# light_controller.net
KiCad netlist of a schematic drawn in EAGLE
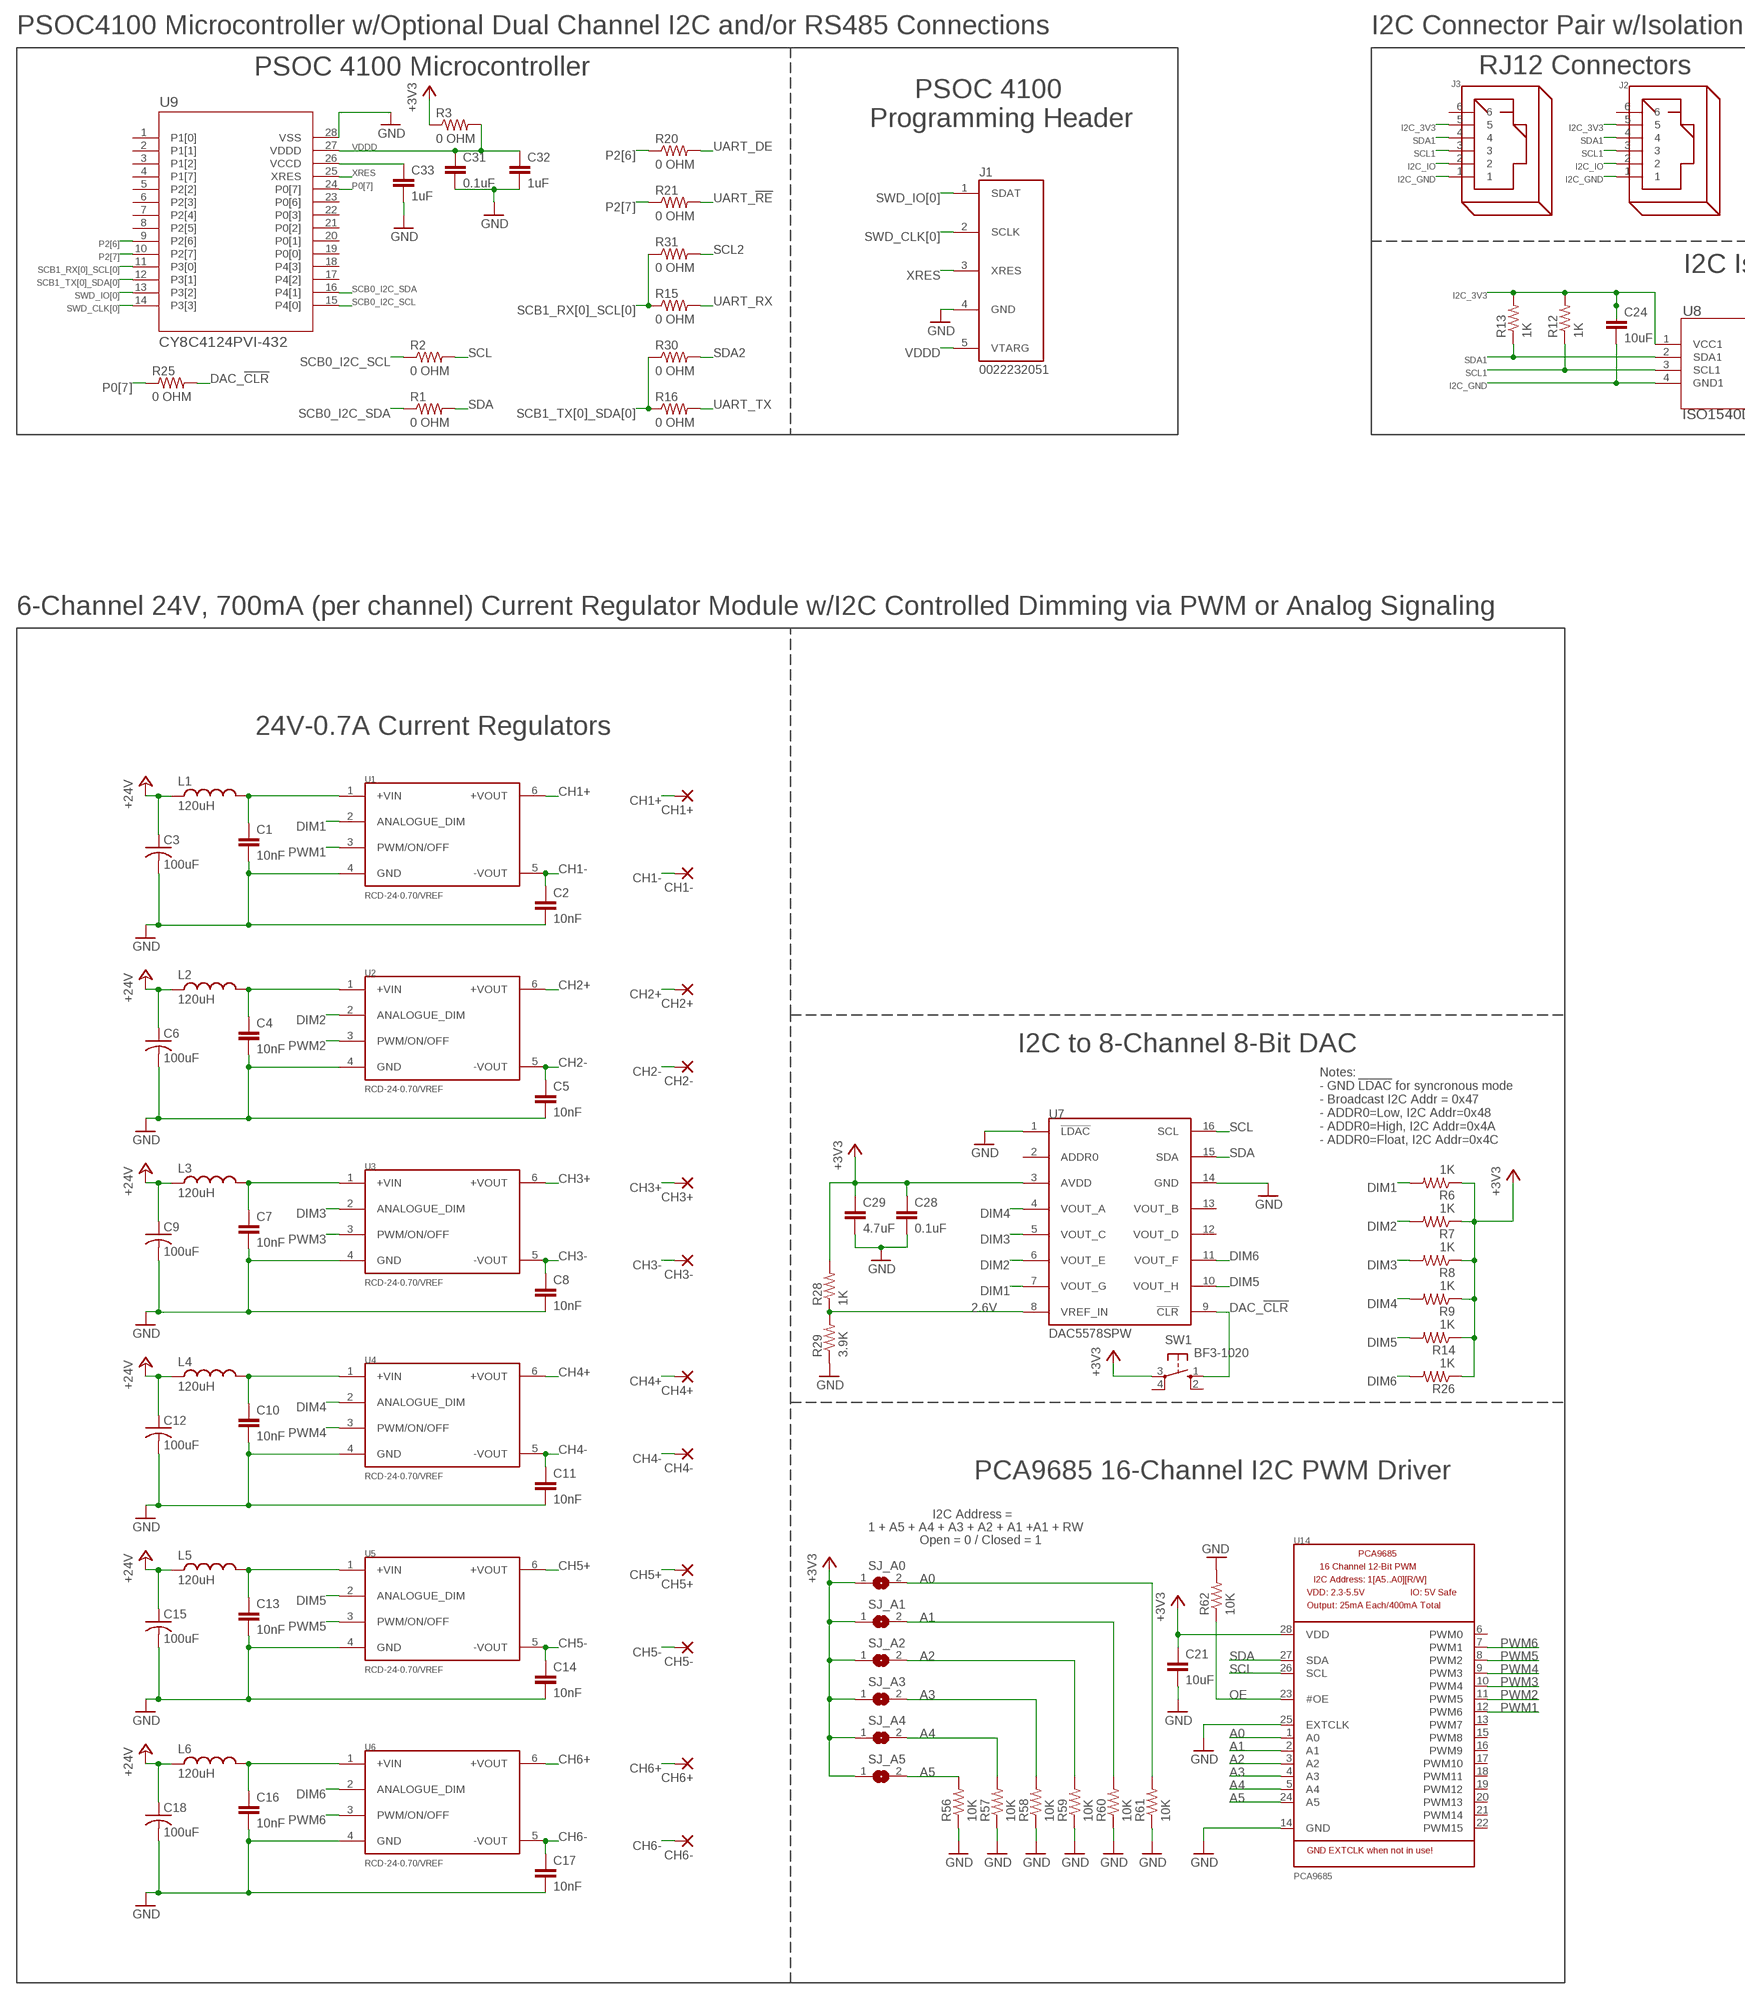
[diagram p0: schematic, sheet 1, part 1 of 2]
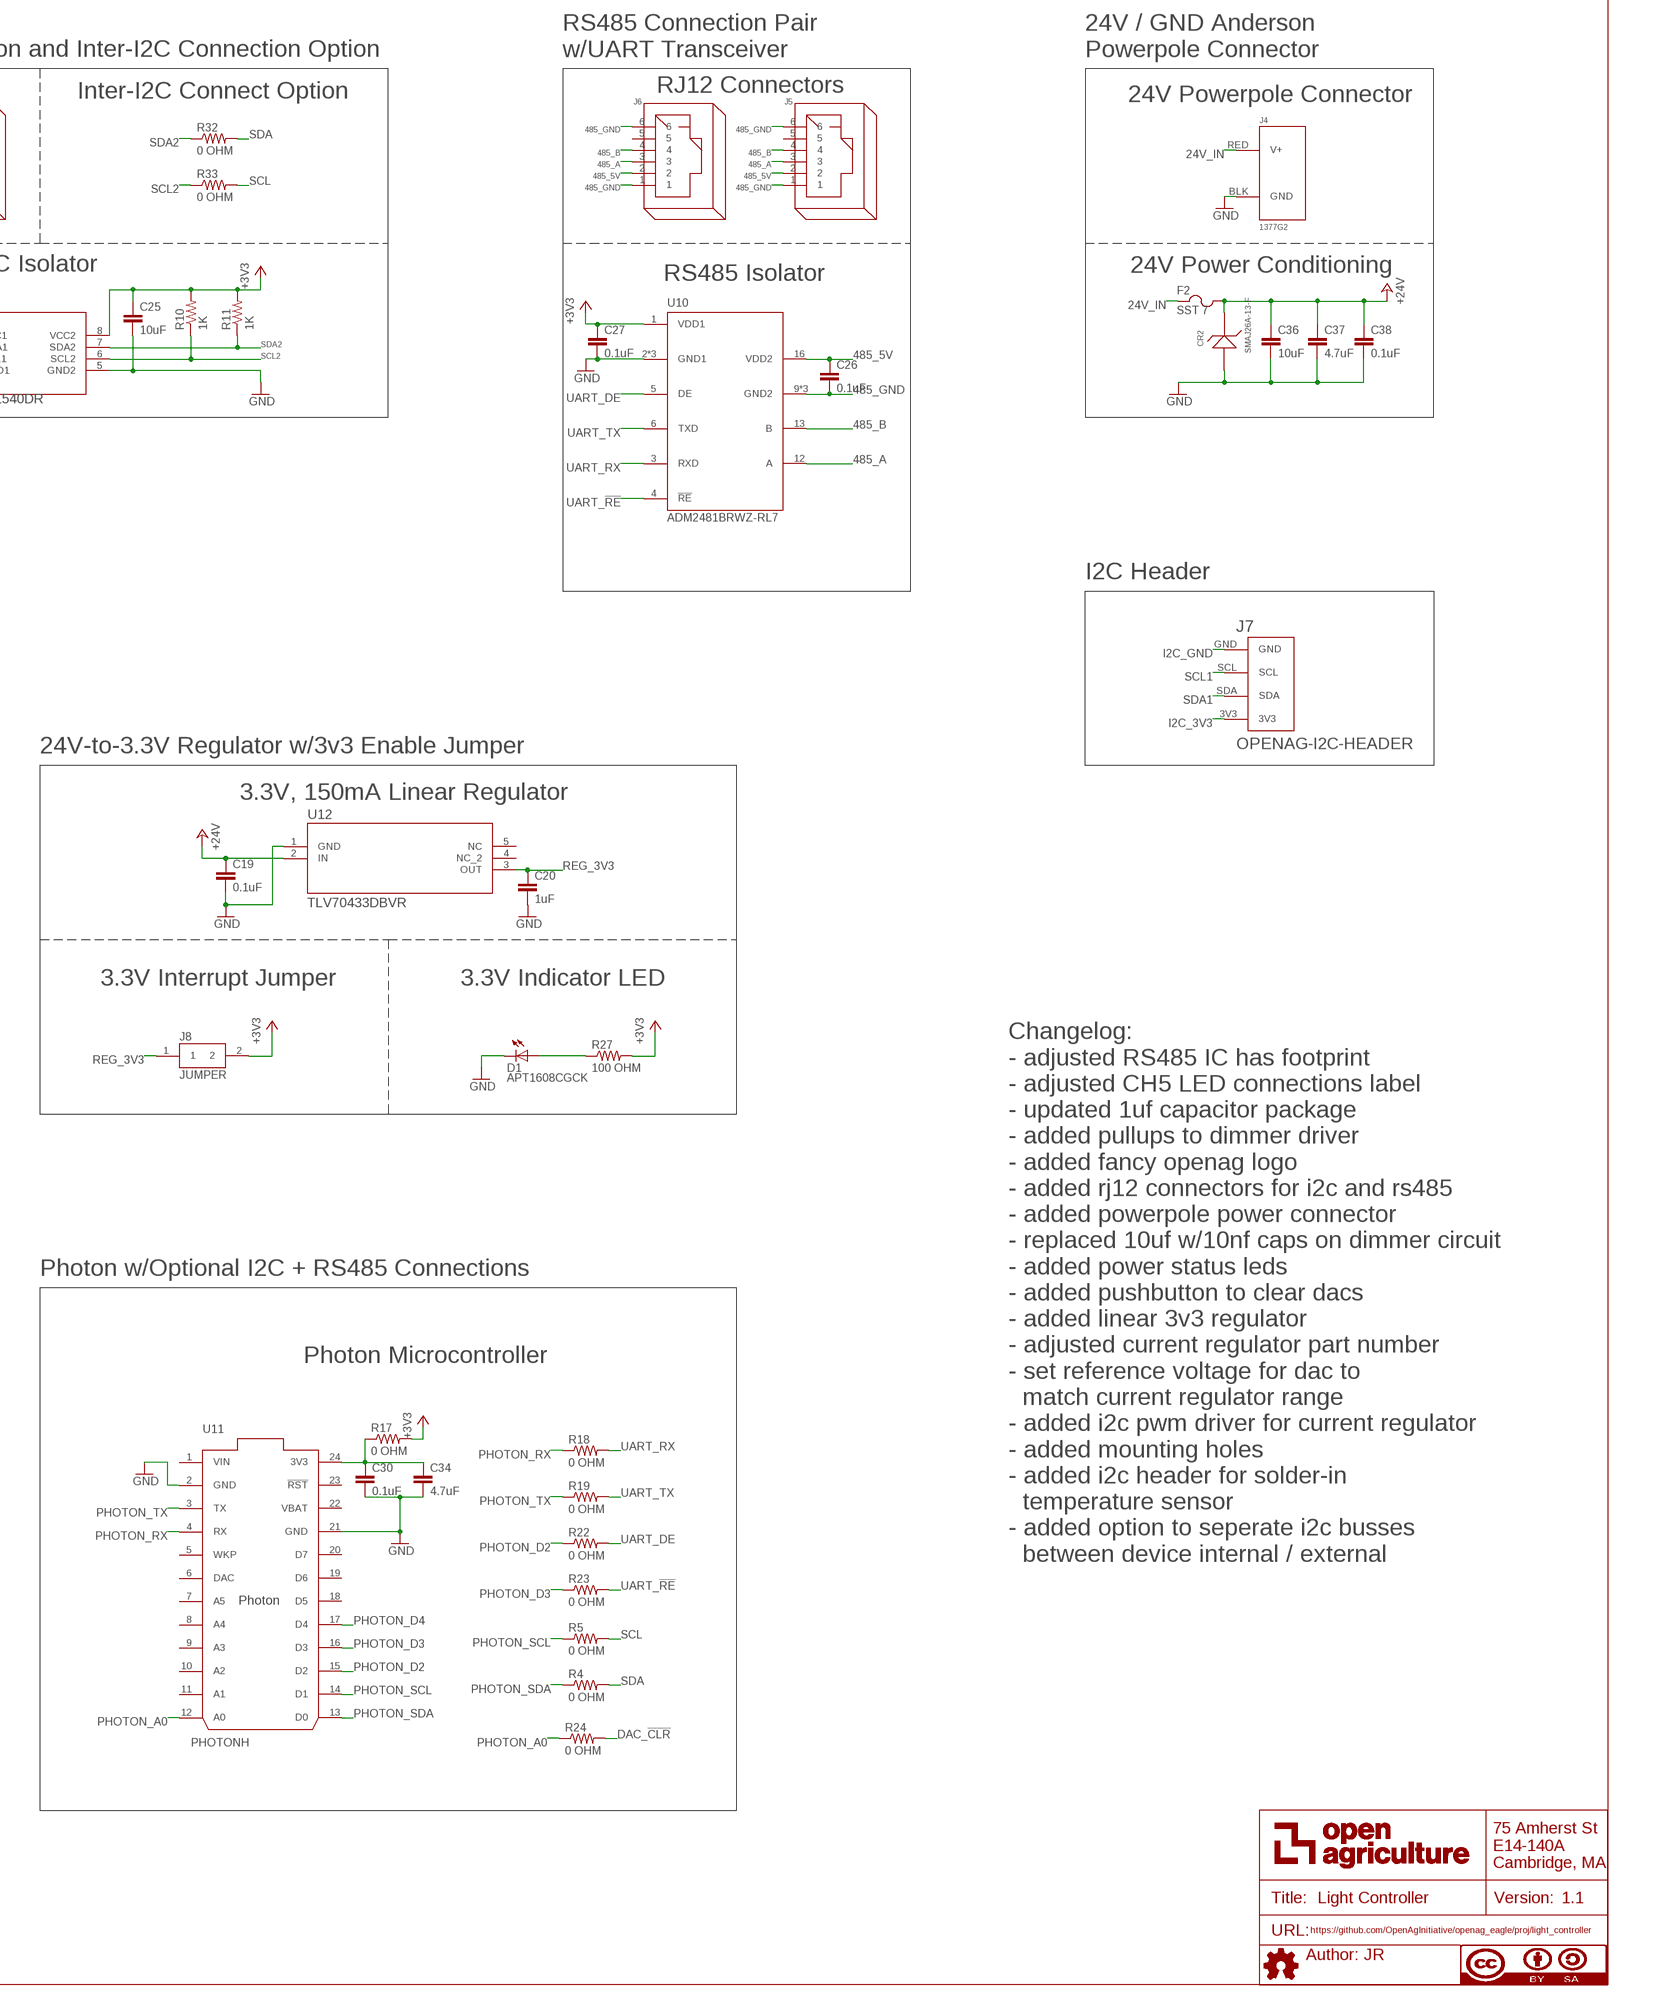
[diagram p1: schematic, sheet 1, part 2 of 2]

(export (version "E")
  (design (tool "Eeschema 10.0.6"))
  (components
    (comp (ref "C1")
      (value "10nF")
      (footprint "eagle-import:C0603")
      (libsource (lib "eagle-import") (part "10NF-C0603C103K5RACTU"))
    )
    (comp (ref "C2")
      (value "10nF")
      (footprint "eagle-import:C0603")
      (libsource (lib "eagle-import") (part "10NF-C0603C103K5RACTU"))
    )
    (comp (ref "C3")
      (value "100uF")
      (footprint "eagle-import:EEE-1HA101UP")
      (libsource (lib "eagle-import") (part "100UF-EEE-1HA101UP"))
    )
    (comp (ref "C4")
      (value "10nF")
      (footprint "eagle-import:C0603")
      (libsource (lib "eagle-import") (part "10NF-C0603C103K5RACTU"))
    )
    (comp (ref "C5")
      (value "10nF")
      (footprint "eagle-import:C0603")
      (libsource (lib "eagle-import") (part "10NF-C0603C103K5RACTU"))
    )
    (comp (ref "C6")
      (value "100uF")
      (footprint "eagle-import:EEE-1HA101UP")
      (libsource (lib "eagle-import") (part "100UF-EEE-1HA101UP"))
    )
    (comp (ref "C7")
      (value "10nF")
      (footprint "eagle-import:C0603")
      (libsource (lib "eagle-import") (part "10NF-C0603C103K5RACTU"))
    )
    (comp (ref "C8")
      (value "10nF")
      (footprint "eagle-import:C0603")
      (libsource (lib "eagle-import") (part "10NF-C0603C103K5RACTU"))
    )
    (comp (ref "C9")
      (value "100uF")
      (footprint "eagle-import:EEE-1HA101UP")
      (libsource (lib "eagle-import") (part "100UF-EEE-1HA101UP"))
    )
    (comp (ref "C10")
      (value "10nF")
      (footprint "eagle-import:C0603")
      (libsource (lib "eagle-import") (part "10NF-C0603C103K5RACTU"))
    )
    (comp (ref "C11")
      (value "10nF")
      (footprint "eagle-import:C0603")
      (libsource (lib "eagle-import") (part "10NF-C0603C103K5RACTU"))
    )
    (comp (ref "C12")
      (value "100uF")
      (footprint "eagle-import:EEE-1HA101UP")
      (libsource (lib "eagle-import") (part "100UF-EEE-1HA101UP"))
    )
    (comp (ref "C13")
      (value "10nF")
      (footprint "eagle-import:C0603")
      (libsource (lib "eagle-import") (part "10NF-C0603C103K5RACTU"))
    )
    (comp (ref "C14")
      (value "10nF")
      (footprint "eagle-import:C0603")
      (libsource (lib "eagle-import") (part "10NF-C0603C103K5RACTU"))
    )
    (comp (ref "C15")
      (value "100uF")
      (footprint "eagle-import:EEE-1HA101UP")
      (libsource (lib "eagle-import") (part "100UF-EEE-1HA101UP"))
    )
    (comp (ref "C16")
      (value "10nF")
      (footprint "eagle-import:C0603")
      (libsource (lib "eagle-import") (part "10NF-C0603C103K5RACTU"))
    )
    (comp (ref "C17")
      (value "10nF")
      (footprint "eagle-import:C0603")
      (libsource (lib "eagle-import") (part "10NF-C0603C103K5RACTU"))
    )
    (comp (ref "C18")
      (value "100uF")
      (footprint "eagle-import:EEE-1HA101UP")
      (libsource (lib "eagle-import") (part "100UF-EEE-1HA101UP"))
    )
    (comp (ref "C19")
      (value "0.1uF")
      (footprint "eagle-import:C0603")
      (libsource (lib "eagle-import") (part "0.1UF-C0603C104K5RACTU"))
    )
    (comp (ref "C20")
      (value "1uF")
      (footprint "eagle-import:C0603")
      (libsource (lib "eagle-import") (part "1UF-CL10A105KB8NNNC"))
    )
    (comp (ref "C21")
      (value "10uF")
      (footprint "eagle-import:C0805")
      (libsource (lib "eagle-import") (part "10UF-GMK212BBJ106KG-T"))
    )
    (comp (ref "C24")
      (value "10uF")
      (footprint "eagle-import:C0805")
      (libsource (lib "eagle-import") (part "10UF-GMK212BBJ106KG-T"))
    )
    (comp (ref "C25")
      (value "10uF")
      (footprint "eagle-import:C0805")
      (libsource (lib "eagle-import") (part "10UF-GMK212BBJ106KG-T"))
    )
    (comp (ref "C26")
      (value "0.1uF")
      (footprint "eagle-import:C0603")
      (libsource (lib "eagle-import") (part "0.1UF-C0603C104K5RACTU"))
    )
    (comp (ref "C27")
      (value "0.1uF")
      (footprint "eagle-import:C0603")
      (libsource (lib "eagle-import") (part "0.1UF-C0603C104K5RACTU"))
    )
    (comp (ref "C28")
      (value "0.1uF")
      (footprint "eagle-import:C0603")
      (libsource (lib "eagle-import") (part "0.1UF-C0603C104K5RACTU"))
    )
    (comp (ref "C29")
      (value "4.7uF")
      (footprint "eagle-import:C0805")
      (libsource (lib "eagle-import") (part "4.7UF-CL21A475KBQNNNE"))
    )
    (comp (ref "C30")
      (value "0.1uF")
      (footprint "eagle-import:C0603")
      (libsource (lib "eagle-import") (part "0.1UF-C0603C104K5RACTU"))
    )
    (comp (ref "C31")
      (value "0.1uF")
      (footprint "eagle-import:C0603")
      (libsource (lib "eagle-import") (part "0.1UF-C0603C104K5RACTU"))
    )
    (comp (ref "C32")
      (value "1uF")
      (footprint "eagle-import:C0603")
      (libsource (lib "eagle-import") (part "1UF-CL10A105KB8NNNC"))
    )
    (comp (ref "C33")
      (value "1uF")
      (footprint "eagle-import:C0603")
      (libsource (lib "eagle-import") (part "1UF-CL10A105KB8NNNC"))
    )
    (comp (ref "C34")
      (value "4.7uF")
      (footprint "eagle-import:C0805")
      (libsource (lib "eagle-import") (part "4.7UF-CL21A475KBQNNNE"))
    )
    (comp (ref "C36")
      (value "10uF")
      (footprint "eagle-import:C0805")
      (libsource (lib "eagle-import") (part "10UF-GMK212BBJ106KG-T"))
    )
    (comp (ref "C37")
      (value "4.7uF")
      (footprint "eagle-import:C0805")
      (libsource (lib "eagle-import") (part "4.7UF-CL21A475KBQNNNE"))
    )
    (comp (ref "C38")
      (value "0.1uF")
      (footprint "eagle-import:C0603")
      (libsource (lib "eagle-import") (part "0.1UF-C0603C104K5RACTU"))
    )
    (comp (ref "CH1+")
      (value "3,17/1,3")
      (footprint "eagle-import:3,17_1,3")
      (libsource (lib "eagle-import") (part "3,17/1,3"))
    )
    (comp (ref "CH1-")
      (value "3,17/1,3")
      (footprint "eagle-import:3,17_1,3")
      (libsource (lib "eagle-import") (part "3,17/1,3"))
    )
    (comp (ref "CH2+")
      (value "3,17/1,3")
      (footprint "eagle-import:3,17_1,3")
      (libsource (lib "eagle-import") (part "3,17/1,3"))
    )
    (comp (ref "CH2-")
      (value "3,17/1,3")
      (footprint "eagle-import:3,17_1,3")
      (libsource (lib "eagle-import") (part "3,17/1,3"))
    )
    (comp (ref "CH3+")
      (value "3,17/1,3")
      (footprint "eagle-import:3,17_1,3")
      (libsource (lib "eagle-import") (part "3,17/1,3"))
    )
    (comp (ref "CH3-")
      (value "3,17/1,3")
      (footprint "eagle-import:3,17_1,3")
      (libsource (lib "eagle-import") (part "3,17/1,3"))
    )
    (comp (ref "CH4+")
      (value "3,17/1,3")
      (footprint "eagle-import:3,17_1,3")
      (libsource (lib "eagle-import") (part "3,17/1,3"))
    )
    (comp (ref "CH4-")
      (value "3,17/1,3")
      (footprint "eagle-import:3,17_1,3")
      (libsource (lib "eagle-import") (part "3,17/1,3"))
    )
    (comp (ref "CH5+")
      (value "3,17/1,3")
      (footprint "eagle-import:3,17_1,3")
      (libsource (lib "eagle-import") (part "3,17/1,3"))
    )
    (comp (ref "CH5-")
      (value "3,17/1,3")
      (footprint "eagle-import:3,17_1,3")
      (libsource (lib "eagle-import") (part "3,17/1,3"))
    )
    (comp (ref "CH6+")
      (value "3,17/1,3")
      (footprint "eagle-import:3,17_1,3")
      (libsource (lib "eagle-import") (part "3,17/1,3"))
    )
    (comp (ref "CH6-")
      (value "3,17/1,3")
      (footprint "eagle-import:3,17_1,3")
      (libsource (lib "eagle-import") (part "3,17/1,3"))
    )
    (comp (ref "CR2")
      (value "SMAJ26A-13-F")
      (footprint "eagle-import:SMA")
      (libsource (lib "eagle-import") (part "SMAJ26A-13-F"))
    )
    (comp (ref "D1")
      (value "APT1608CGCK")
      (footprint "eagle-import:CHIPLED_0603")
      (libsource (lib "eagle-import") (part "APT1608CGCK"))
    )
    (comp (ref "F2")
      (value "SST 7")
      (footprint "eagle-import:SS")
      (libsource (lib "eagle-import") (part "SST_7"))
    )
    (comp (ref "FRAME1")
      (value "DOCFIELD")
      (footprint "eagle-import:DOCFIELD")
      (description "Controls 6 channels of 24V, 700mA for LED strings that can be interfaced via i2c, rs485, and/or wifi.")
      (fields
        (field (name "TITLE") "Example Template")
        (field (name "AUTHOR") "XX")
        (field (name "VER") "1.0")
        (field (name "URL") "https://github.com/OpenAgInitiative/openag_eagle_template")
        (field (name "AUTHOR_1") "JR")
        (field (name "TITLE_1") "Light Controller")
        (field (name "URL_1") "https://github.com/OpenAgInitiative/openag_eagle/proj/light_controller")
        (field (name "VER_1") "1.1")
      )
      (libsource (lib "eagle-import") (part "DOCFIELD"))
    )
    (comp (ref "J1")
      (value "0022232051")
      (footprint "eagle-import:22-23-2051")
      (libsource (lib "eagle-import") (part "MINI-PROG3-5POS-MATING-CONNECTOR"))
    )
    (comp (ref "J2")
      (value "OPENAG-I2C-RJ12")
      (footprint "eagle-import:OPENAG-I2C-RJ12")
      (fields (field (name "MPN") "A-2004-1-4-LP-N-R"))
      (libsource (lib "eagle-import") (part "OPENAG-I2C-RJ12"))
    )
    (comp (ref "J3")
      (value "OPENAG-I2C-RJ12")
      (footprint "eagle-import:OPENAG-I2C-RJ12")
      (fields (field (name "MPN") "A-2004-1-4-LP-N-R"))
      (libsource (lib "eagle-import") (part "OPENAG-I2C-RJ12"))
    )
    (comp (ref "J4")
      (value "1377G2")
      (footprint "eagle-import:1377G2")
      (libsource (lib "eagle-import") (part "1377G21377G2"))
    )
    (comp (ref "J5")
      (value "OPENAG-RS485-RJ12")
      (footprint "eagle-import:OPENAG-RS485-RJ12")
      (libsource (lib "eagle-import") (part "OPENAG-RS485-RJ12"))
    )
    (comp (ref "J6")
      (value "OPENAG-RS485-RJ12")
      (footprint "eagle-import:OPENAG-RS485-RJ12")
      (libsource (lib "eagle-import") (part "OPENAG-RS485-RJ12"))
    )
    (comp (ref "J7")
      (value "OPENAG-I2C-HEADER")
      (footprint "eagle-import:OPENAG-I2C-HEADER")
      (libsource (lib "eagle-import") (part "OPENAG-I2C-HEADER"))
    )
    (comp (ref "J8")
      (value "JUMPER")
      (footprint "eagle-import:1X2-100-MIL-HEADER")
      (libsource (lib "eagle-import") (part "100-MIL-HEADER-JUMPER"))
    )
    (comp (ref "L1")
      (value "120uH")
      (footprint "eagle-import:74404064121")
      (libsource (lib "eagle-import") (part "120UH-74404064121"))
    )
    (comp (ref "L2")
      (value "120uH")
      (footprint "eagle-import:74404064121")
      (libsource (lib "eagle-import") (part "120UH-74404064121"))
    )
    (comp (ref "L3")
      (value "120uH")
      (footprint "eagle-import:74404064121")
      (libsource (lib "eagle-import") (part "120UH-74404064121"))
    )
    (comp (ref "L4")
      (value "120uH")
      (footprint "eagle-import:74404064121")
      (libsource (lib "eagle-import") (part "120UH-74404064121"))
    )
    (comp (ref "L5")
      (value "120uH")
      (footprint "eagle-import:74404064121")
      (libsource (lib "eagle-import") (part "120UH-74404064121"))
    )
    (comp (ref "L6")
      (value "120uH")
      (footprint "eagle-import:74404064121")
      (libsource (lib "eagle-import") (part "120UH-74404064121"))
    )
    (comp (ref "R1")
      (value "0 OHM")
      (footprint "eagle-import:RC0603N")
      (libsource (lib "eagle-import") (part "0OHM-RC0603JR-070RL"))
    )
    (comp (ref "R2")
      (value "0 OHM")
      (footprint "eagle-import:RC0603N")
      (libsource (lib "eagle-import") (part "0OHM-RC0603JR-070RL"))
    )
    (comp (ref "R3")
      (value "0 OHM")
      (footprint "eagle-import:RC0603N")
      (libsource (lib "eagle-import") (part "0OHM-RC0603JR-070RL"))
    )
    (comp (ref "R4")
      (value "0 OHM")
      (footprint "eagle-import:RC0603N")
      (libsource (lib "eagle-import") (part "0OHM-RC0603JR-070RL"))
    )
    (comp (ref "R5")
      (value "0 OHM")
      (footprint "eagle-import:RC0603N")
      (libsource (lib "eagle-import") (part "0OHM-RC0603JR-070RL"))
    )
    (comp (ref "R6")
      (value "1K")
      (footprint "eagle-import:RC0603N")
      (libsource (lib "eagle-import") (part "1K-ERJ-PB3D1001V"))
    )
    (comp (ref "R7")
      (value "1K")
      (footprint "eagle-import:RC0603N")
      (libsource (lib "eagle-import") (part "1K-ERJ-PB3D1001V"))
    )
    (comp (ref "R8")
      (value "1K")
      (footprint "eagle-import:RC0603N")
      (libsource (lib "eagle-import") (part "1K-ERJ-PB3D1001V"))
    )
    (comp (ref "R9")
      (value "1K")
      (footprint "eagle-import:RC0603N")
      (libsource (lib "eagle-import") (part "1K-ERJ-PB3D1001V"))
    )
    (comp (ref "R10")
      (value "1K")
      (footprint "eagle-import:RC0603N")
      (libsource (lib "eagle-import") (part "1K-ERJ-PB3D1001V"))
    )
    (comp (ref "R11")
      (value "1K")
      (footprint "eagle-import:RC0603N")
      (libsource (lib "eagle-import") (part "1K-ERJ-PB3D1001V"))
    )
    (comp (ref "R12")
      (value "1K")
      (footprint "eagle-import:RC0603N")
      (libsource (lib "eagle-import") (part "1K-ERJ-PB3D1001V"))
    )
    (comp (ref "R13")
      (value "1K")
      (footprint "eagle-import:RC0603N")
      (libsource (lib "eagle-import") (part "1K-ERJ-PB3D1001V"))
    )
    (comp (ref "R14")
      (value "1K")
      (footprint "eagle-import:RC0603N")
      (libsource (lib "eagle-import") (part "1K-ERJ-PB3D1001V"))
    )
    (comp (ref "R15")
      (value "0 OHM")
      (footprint "eagle-import:RC0603N")
      (libsource (lib "eagle-import") (part "0OHM-RC0603JR-070RL"))
    )
    (comp (ref "R16")
      (value "0 OHM")
      (footprint "eagle-import:RC0603N")
      (libsource (lib "eagle-import") (part "0OHM-RC0603JR-070RL"))
    )
    (comp (ref "R17")
      (value "0 OHM")
      (footprint "eagle-import:RC0603N")
      (libsource (lib "eagle-import") (part "0OHM-RC0603JR-070RL"))
    )
    (comp (ref "R18")
      (value "0 OHM")
      (footprint "eagle-import:RC0603N")
      (libsource (lib "eagle-import") (part "0OHM-RC0603JR-070RL"))
    )
    (comp (ref "R19")
      (value "0 OHM")
      (footprint "eagle-import:RC0603N")
      (libsource (lib "eagle-import") (part "0OHM-RC0603JR-070RL"))
    )
    (comp (ref "R20")
      (value "0 OHM")
      (footprint "eagle-import:RC0603N")
      (libsource (lib "eagle-import") (part "0OHM-RC0603JR-070RL"))
    )
    (comp (ref "R21")
      (value "0 OHM")
      (footprint "eagle-import:RC0603N")
      (libsource (lib "eagle-import") (part "0OHM-RC0603JR-070RL"))
    )
    (comp (ref "R22")
      (value "0 OHM")
      (footprint "eagle-import:RC0603N")
      (libsource (lib "eagle-import") (part "0OHM-RC0603JR-070RL"))
    )
    (comp (ref "R23")
      (value "0 OHM")
      (footprint "eagle-import:RC0603N")
      (libsource (lib "eagle-import") (part "0OHM-RC0603JR-070RL"))
    )
    (comp (ref "R24")
      (value "0 OHM")
      (footprint "eagle-import:RC0603N")
      (libsource (lib "eagle-import") (part "0OHM-RC0603JR-070RL"))
    )
    (comp (ref "R25")
      (value "0 OHM")
      (footprint "eagle-import:RC0603N")
      (libsource (lib "eagle-import") (part "0OHM-RC0603JR-070RL"))
    )
    (comp (ref "R26")
      (value "1K")
      (footprint "eagle-import:RC0603N")
      (libsource (lib "eagle-import") (part "1K-ERJ-PB3D1001V"))
    )
    (comp (ref "R27")
      (value "100 OHM")
      (footprint "eagle-import:RC0603N")
      (libsource (lib "eagle-import") (part "100OHM-RC0603JR-07100RL"))
    )
    (comp (ref "R28")
      (value "1K")
      (footprint "eagle-import:RC0603N")
      (libsource (lib "eagle-import") (part "1K-ERJ-PB3D1001V"))
    )
    (comp (ref "R29")
      (value "3.9K")
      (footprint "eagle-import:RC0603N")
      (libsource (lib "eagle-import") (part "3.9K-RC0603JR-073K9L"))
    )
    (comp (ref "R30")
      (value "0 OHM")
      (footprint "eagle-import:RC0603N")
      (libsource (lib "eagle-import") (part "0OHM-RC0603JR-070RL"))
    )
    (comp (ref "R31")
      (value "0 OHM")
      (footprint "eagle-import:RC0603N")
      (libsource (lib "eagle-import") (part "0OHM-RC0603JR-070RL"))
    )
    (comp (ref "R32")
      (value "0 OHM")
      (footprint "eagle-import:RC0603N")
      (libsource (lib "eagle-import") (part "0OHM-RC0603JR-070RL"))
    )
    (comp (ref "R33")
      (value "0 OHM")
      (footprint "eagle-import:RC0603N")
      (libsource (lib "eagle-import") (part "0OHM-RC0603JR-070RL"))
    )
    (comp (ref "R56")
      (value "10K")
      (footprint "eagle-import:RC0603N")
      (libsource (lib "eagle-import") (part "10K-ERJ-3EKF1002V"))
    )
    (comp (ref "R57")
      (value "10K")
      (footprint "eagle-import:RC0603N")
      (libsource (lib "eagle-import") (part "10K-ERJ-3EKF1002V"))
    )
    (comp (ref "R58")
      (value "10K")
      (footprint "eagle-import:RC0603N")
      (libsource (lib "eagle-import") (part "10K-ERJ-3EKF1002V"))
    )
    (comp (ref "R59")
      (value "10K")
      (footprint "eagle-import:RC0603N")
      (libsource (lib "eagle-import") (part "10K-ERJ-3EKF1002V"))
    )
    (comp (ref "R60")
      (value "10K")
      (footprint "eagle-import:RC0603N")
      (libsource (lib "eagle-import") (part "10K-ERJ-3EKF1002V"))
    )
    (comp (ref "R61")
      (value "10K")
      (footprint "eagle-import:RC0603N")
      (libsource (lib "eagle-import") (part "10K-ERJ-3EKF1002V"))
    )
    (comp (ref "R62")
      (value "10K")
      (footprint "eagle-import:RC0603N")
      (libsource (lib "eagle-import") (part "10K-ERJ-3EKF1002V"))
    )
    (comp (ref "SJ_A0")
      (value "SOLDERJUMPERREFLOW_NOPASTE")
      (footprint "eagle-import:SOLDERJUMPER_REFLOW_NOPASTE")
      (libsource (lib "eagle-import") (part "SOLDERJUMPERREFLOW_NOPASTE"))
    )
    (comp (ref "SJ_A1")
      (value "SOLDERJUMPERREFLOW_NOPASTE")
      (footprint "eagle-import:SOLDERJUMPER_REFLOW_NOPASTE")
      (libsource (lib "eagle-import") (part "SOLDERJUMPERREFLOW_NOPASTE"))
    )
    (comp (ref "SJ_A2")
      (value "SOLDERJUMPERREFLOW_NOPASTE")
      (footprint "eagle-import:SOLDERJUMPER_REFLOW_NOPASTE")
      (libsource (lib "eagle-import") (part "SOLDERJUMPERREFLOW_NOPASTE"))
    )
    (comp (ref "SJ_A3")
      (value "SOLDERJUMPERREFLOW_NOPASTE")
      (footprint "eagle-import:SOLDERJUMPER_REFLOW_NOPASTE")
      (libsource (lib "eagle-import") (part "SOLDERJUMPERREFLOW_NOPASTE"))
    )
    (comp (ref "SJ_A4")
      (value "SOLDERJUMPERREFLOW_NOPASTE")
      (footprint "eagle-import:SOLDERJUMPER_REFLOW_NOPASTE")
      (libsource (lib "eagle-import") (part "SOLDERJUMPERREFLOW_NOPASTE"))
    )
    (comp (ref "SJ_A5")
      (value "SOLDERJUMPERREFLOW_NOPASTE")
      (footprint "eagle-import:SOLDERJUMPER_REFLOW_NOPASTE")
      (libsource (lib "eagle-import") (part "SOLDERJUMPERREFLOW_NOPASTE"))
    )
    (comp (ref "SW1")
      (value "BF3-1020")
      (footprint "eagle-import:B3F-10XX")
      (libsource (lib "eagle-import") (part "BF3-1020"))
    )
    (comp (ref "U1")
      (value "RCD-24-0.70/VREF")
      (footprint "eagle-import:RCD-24-PINNED")
      (libsource (lib "eagle-import") (part "RCD-24-0.70/VREF"))
    )
    (comp (ref "U2")
      (value "RCD-24-0.70/VREF")
      (footprint "eagle-import:RCD-24-PINNED")
      (libsource (lib "eagle-import") (part "RCD-24-0.70/VREF"))
    )
    (comp (ref "U3")
      (value "RCD-24-0.70/VREF")
      (footprint "eagle-import:RCD-24-PINNED")
      (libsource (lib "eagle-import") (part "RCD-24-0.70/VREF"))
    )
    (comp (ref "U4")
      (value "RCD-24-0.70/VREF")
      (footprint "eagle-import:RCD-24-PINNED")
      (libsource (lib "eagle-import") (part "RCD-24-0.70/VREF"))
    )
    (comp (ref "U5")
      (value "RCD-24-0.70/VREF")
      (footprint "eagle-import:RCD-24-PINNED")
      (libsource (lib "eagle-import") (part "RCD-24-0.70/VREF"))
    )
    (comp (ref "U6")
      (value "RCD-24-0.70/VREF")
      (footprint "eagle-import:RCD-24-PINNED")
      (libsource (lib "eagle-import") (part "RCD-24-0.70/VREF"))
    )
    (comp (ref "U7")
      (value "DAC5578SPW")
      (footprint "eagle-import:TSSOP16")
      (libsource (lib "eagle-import") (part "DAC5578SPW"))
    )
    (comp (ref "U8")
      (value "ISO1540DR")
      (footprint "eagle-import:D8")
      (libsource (lib "eagle-import") (part "ISO1540DR"))
    )
    (comp (ref "U9")
      (value "CY8C4124PVI-432")
      (footprint "eagle-import:SSOP-28")
      (libsource (lib "eagle-import") (part "CY8C4124PVI-432"))
    )
    (comp (ref "U10")
      (value "ADM2481BRWZ-RL7")
      (footprint "eagle-import:SOIC16LWB")
      (libsource (lib "eagle-import") (part "ADM2481BRWZ-RL7"))
    )
    (comp (ref "U11")
      (value "PHOTONH")
      (footprint "eagle-import:PHOTON")
      (libsource (lib "eagle-import") (part "PHOTONHPHOTONH"))
    )
    (comp (ref "U12")
      (value "TLV70433DBVR")
      (footprint "eagle-import:DBV5-M")
      (libsource (lib "eagle-import") (part "TLV70433DBVRDBV5-M"))
    )
    (comp (ref "U14")
      (value "PCA9685")
      (footprint "eagle-import:TSSOP28")
      (libsource (lib "eagle-import") (part "PCA9685PW/Q900,118"))
    )
  )
  (nets
    (net (code "1") (name "+3V3") (class "Default")
      (node (ref "C21") (pin "1") (pinfunction "1_1") (pintype "passive"))
      (node (ref "C25") (pin "1") (pinfunction "1_1") (pintype "passive"))
      (node (ref "C27") (pin "1") (pinfunction "1_1") (pintype "passive"))
      (node (ref "C28") (pin "1") (pinfunction "1_1") (pintype "passive"))
      (node (ref "C29") (pin "1") (pinfunction "1_1") (pintype "passive"))
      (node (ref "J8") (pin "2") (pinfunction "2_2") (pintype "bidirectional"))
      (node (ref "R10") (pin "2") (pinfunction "2_2") (pintype "passive"))
      (node (ref "R11") (pin "2") (pinfunction "2_2") (pintype "passive"))
      (node (ref "R14") (pin "1") (pinfunction "1_1") (pintype "passive"))
      (node (ref "R17") (pin "2") (pinfunction "2_2") (pintype "passive"))
      (node (ref "R26") (pin "1") (pinfunction "1_1") (pintype "passive"))
      (node (ref "R27") (pin "2") (pinfunction "2_2") (pintype "passive"))
      (node (ref "R28") (pin "2") (pinfunction "2_2") (pintype "passive"))
      (node (ref "R3") (pin "1") (pinfunction "1_1") (pintype "passive"))
      (node (ref "R6") (pin "1") (pinfunction "1_1") (pintype "passive"))
      (node (ref "R7") (pin "1") (pinfunction "1_1") (pintype "passive"))
      (node (ref "R8") (pin "1") (pinfunction "1_1") (pintype "passive"))
      (node (ref "R9") (pin "1") (pinfunction "1_1") (pintype "passive"))
      (node (ref "SJ_A0") (pin "1") (pinfunction "1_1") (pintype "passive"))
      (node (ref "SJ_A1") (pin "1") (pinfunction "1_1") (pintype "passive"))
      (node (ref "SJ_A2") (pin "1") (pinfunction "1_1") (pintype "passive"))
      (node (ref "SJ_A3") (pin "1") (pinfunction "1_1") (pintype "passive"))
      (node (ref "SJ_A4") (pin "1") (pinfunction "1_1") (pintype "passive"))
      (node (ref "SJ_A5") (pin "1") (pinfunction "1_1") (pintype "passive"))
      (node (ref "SW1") (pin "3") (pinfunction "P_3") (pintype "passive"))
      (node (ref "U10") (pin "1") (pinfunction "VDD1_1") (pintype "bidirectional"))
      (node (ref "U14") (pin "28") (pinfunction "VDD_28") (pintype "power_in"))
      (node (ref "U7") (pin "3") (pinfunction "AVDD_3") (pintype "bidirectional"))
      (node (ref "U8") (pin "8") (pinfunction "VCC2_8") (pintype "power_in"))
    )
    (net (code "2") (name "+24V") (class "Default")
      (node (ref "C12") (pin "+") (pinfunction "1(+)_+") (pintype "passive"))
      (node (ref "C15") (pin "+") (pinfunction "1(+)_+") (pintype "passive"))
      (node (ref "C18") (pin "+") (pinfunction "1(+)_+") (pintype "passive"))
      (node (ref "C19") (pin "1") (pinfunction "1_1") (pintype "passive"))
      (node (ref "C3") (pin "+") (pinfunction "1(+)_+") (pintype "passive"))
      (node (ref "C36") (pin "1") (pinfunction "1_1") (pintype "passive"))
      (node (ref "C37") (pin "1") (pinfunction "1_1") (pintype "passive"))
      (node (ref "C38") (pin "1") (pinfunction "1_1") (pintype "passive"))
      (node (ref "C6") (pin "+") (pinfunction "1(+)_+") (pintype "passive"))
      (node (ref "C9") (pin "+") (pinfunction "1(+)_+") (pintype "passive"))
      (node (ref "CR2") (pin "1") (pinfunction "P$2_1") (pintype "bidirectional"))
      (node (ref "F2") (pin "2") (pinfunction "2_2") (pintype "passive"))
      (node (ref "L1") (pin "1") (pinfunction "1_1") (pintype "passive"))
      (node (ref "L2") (pin "1") (pinfunction "1_1") (pintype "passive"))
      (node (ref "L3") (pin "1") (pinfunction "1_1") (pintype "passive"))
      (node (ref "L4") (pin "1") (pinfunction "1_1") (pintype "passive"))
      (node (ref "L5") (pin "1") (pinfunction "1_1") (pintype "passive"))
      (node (ref "L6") (pin "1") (pinfunction "1_1") (pintype "passive"))
      (node (ref "U12") (pin "2") (pinfunction "IN_2") (pintype "input"))
    )
    (net (code "3") (name "/2.6V") (class "Default")
      (node (ref "R28") (pin "1") (pinfunction "1_1") (pintype "passive"))
      (node (ref "R29") (pin "2") (pinfunction "2_2") (pintype "passive"))
      (node (ref "U7") (pin "8") (pinfunction "VREF_IN_8") (pintype "bidirectional"))
    )
    (net (code "4") (name "/A0") (class "Default")
      (node (ref "R61") (pin "2") (pinfunction "2_2") (pintype "passive"))
      (node (ref "SJ_A0") (pin "2") (pinfunction "2_2") (pintype "passive"))
      (node (ref "U14") (pin "1") (pinfunction "A0_1") (pintype "bidirectional"))
    )
    (net (code "5") (name "/A1") (class "Default")
      (node (ref "R60") (pin "2") (pinfunction "2_2") (pintype "passive"))
      (node (ref "SJ_A1") (pin "2") (pinfunction "2_2") (pintype "passive"))
      (node (ref "U14") (pin "2") (pinfunction "A1_2") (pintype "bidirectional"))
    )
    (net (code "6") (name "/A2") (class "Default")
      (node (ref "R59") (pin "2") (pinfunction "2_2") (pintype "passive"))
      (node (ref "SJ_A2") (pin "2") (pinfunction "2_2") (pintype "passive"))
      (node (ref "U14") (pin "3") (pinfunction "A2_3") (pintype "bidirectional"))
    )
    (net (code "7") (name "/A3") (class "Default")
      (node (ref "R58") (pin "2") (pinfunction "2_2") (pintype "passive"))
      (node (ref "SJ_A3") (pin "2") (pinfunction "2_2") (pintype "passive"))
      (node (ref "U14") (pin "4") (pinfunction "A3_4") (pintype "bidirectional"))
    )
    (net (code "8") (name "/A4") (class "Default")
      (node (ref "R57") (pin "2") (pinfunction "2_2") (pintype "passive"))
      (node (ref "SJ_A4") (pin "2") (pinfunction "2_2") (pintype "passive"))
      (node (ref "U14") (pin "5") (pinfunction "A4_5") (pintype "bidirectional"))
    )
    (net (code "9") (name "/A5") (class "Default")
      (node (ref "R56") (pin "2") (pinfunction "2_2") (pintype "passive"))
      (node (ref "SJ_A5") (pin "2") (pinfunction "2_2") (pintype "passive"))
      (node (ref "U14") (pin "24") (pinfunction "A5_24") (pintype "bidirectional"))
    )
    (net (code "10") (name "/DAC_~{CLR}") (class "Default")
      (node (ref "R24") (pin "2") (pinfunction "2_2") (pintype "passive"))
      (node (ref "R25") (pin "2") (pinfunction "2_2") (pintype "passive"))
      (node (ref "SW1") (pin "1") (pinfunction "S_1") (pintype "passive"))
      (node (ref "U7") (pin "9") (pinfunction "~{CLR}_9") (pintype "bidirectional"))
    )
    (net (code "11") (name "/OE") (class "Default")
      (node (ref "R62") (pin "1") (pinfunction "1_1") (pintype "passive"))
      (node (ref "U14") (pin "23") (pinfunction "#OE_23") (pintype "input"))
    )
    (net (code "12") (name "/UART_~{RE}") (class "Default")
      (node (ref "R21") (pin "2") (pinfunction "2_2") (pintype "passive"))
      (node (ref "R23") (pin "2") (pinfunction "2_2") (pintype "passive"))
      (node (ref "U10") (pin "4") (pinfunction "~{RE}_4") (pintype "bidirectional"))
    )
    (net (code "13") (name "/VBAT") (class "Default")
      (node (ref "U11") (pin "22") (pinfunction "VBAT_22") (pintype "power_in"))
    )
    (net (code "14") (name "/VIN") (class "Default")
      (node (ref "U11") (pin "1") (pinfunction "VIN_1") (pintype "power_in"))
    )
    (net (code "15") (name "24V_IN") (class "Default")
      (node (ref "F2") (pin "1") (pinfunction "1_1") (pintype "passive"))
      (node (ref "J4") (pin "RED") (pinfunction "V+_RED") (pintype "power_in"))
    )
    (net (code "16") (name "485_5V") (class "Default")
      (node (ref "C26") (pin "1") (pinfunction "1_1") (pintype "passive"))
      (node (ref "J5") (pin "2") (pinfunction "2_2") (pintype "bidirectional"))
      (node (ref "J6") (pin "2") (pinfunction "2_2") (pintype "bidirectional"))
      (node (ref "U10") (pin "16") (pinfunction "VDD2_16") (pintype "bidirectional"))
    )
    (net (code "17") (name "485_A") (class "Default")
      (node (ref "J5") (pin "3") (pinfunction "3_3") (pintype "bidirectional"))
      (node (ref "J6") (pin "3") (pinfunction "3_3") (pintype "bidirectional"))
      (node (ref "U10") (pin "12") (pinfunction "A_12") (pintype "bidirectional"))
    )
    (net (code "18") (name "485_B") (class "Default")
      (node (ref "J5") (pin "4") (pinfunction "4_4") (pintype "bidirectional"))
      (node (ref "J6") (pin "4") (pinfunction "4_4") (pintype "bidirectional"))
      (node (ref "U10") (pin "13") (pinfunction "B_13") (pintype "bidirectional"))
    )
    (net (code "19") (name "485_GND") (class "Default")
      (node (ref "C26") (pin "2") (pinfunction "2_2") (pintype "passive"))
      (node (ref "J5") (pin "1") (pinfunction "1_1") (pintype "bidirectional"))
      (node (ref "J5") (pin "6") (pinfunction "6_6") (pintype "bidirectional"))
      (node (ref "J6") (pin "1") (pinfunction "1_1") (pintype "bidirectional"))
      (node (ref "J6") (pin "6") (pinfunction "6_6") (pintype "bidirectional"))
      (node (ref "U10") (pin "10") (pinfunction "GND2_10") (pintype "bidirectional"))
      (node (ref "U10") (pin "15") (pinfunction "GND2_15") (pintype "bidirectional"))
      (node (ref "U10") (pin "9") (pinfunction "GND2_9") (pintype "bidirectional"))
    )
    (net (code "20") (name "CH1+") (class "Default")
      (node (ref "CH1+") (pin "1") (pinfunction "P_1") (pintype "passive"))
      (node (ref "U1") (pin "6") (pinfunction "+VOUT_6") (pintype "power_in"))
    )
    (net (code "21") (name "CH1-") (class "Default")
      (node (ref "C2") (pin "1") (pinfunction "1_1") (pintype "passive"))
      (node (ref "CH1-") (pin "1") (pinfunction "P_1") (pintype "passive"))
      (node (ref "U1") (pin "5") (pinfunction "-VOUT_5") (pintype "power_in"))
    )
    (net (code "22") (name "CH2+") (class "Default")
      (node (ref "CH2+") (pin "1") (pinfunction "P_1") (pintype "passive"))
      (node (ref "U2") (pin "6") (pinfunction "+VOUT_6") (pintype "power_in"))
    )
    (net (code "23") (name "CH2-") (class "Default")
      (node (ref "C5") (pin "1") (pinfunction "1_1") (pintype "passive"))
      (node (ref "CH2-") (pin "1") (pinfunction "P_1") (pintype "passive"))
      (node (ref "U2") (pin "5") (pinfunction "-VOUT_5") (pintype "power_in"))
    )
    (net (code "24") (name "CH3+") (class "Default")
      (node (ref "CH3+") (pin "1") (pinfunction "P_1") (pintype "passive"))
      (node (ref "U3") (pin "6") (pinfunction "+VOUT_6") (pintype "power_in"))
    )
    (net (code "25") (name "CH3-") (class "Default")
      (node (ref "C8") (pin "1") (pinfunction "1_1") (pintype "passive"))
      (node (ref "CH3-") (pin "1") (pinfunction "P_1") (pintype "passive"))
      (node (ref "U3") (pin "5") (pinfunction "-VOUT_5") (pintype "power_in"))
    )
    (net (code "26") (name "CH4+") (class "Default")
      (node (ref "CH4+") (pin "1") (pinfunction "P_1") (pintype "passive"))
      (node (ref "U4") (pin "6") (pinfunction "+VOUT_6") (pintype "power_in"))
    )
    (net (code "27") (name "CH4-") (class "Default")
      (node (ref "C11") (pin "1") (pinfunction "1_1") (pintype "passive"))
      (node (ref "CH4-") (pin "1") (pinfunction "P_1") (pintype "passive"))
      (node (ref "U4") (pin "5") (pinfunction "-VOUT_5") (pintype "power_in"))
    )
    (net (code "28") (name "CH5+") (class "Default")
      (node (ref "CH5+") (pin "1") (pinfunction "P_1") (pintype "passive"))
      (node (ref "U5") (pin "6") (pinfunction "+VOUT_6") (pintype "power_in"))
    )
    (net (code "29") (name "CH5-") (class "Default")
      (node (ref "C14") (pin "1") (pinfunction "1_1") (pintype "passive"))
      (node (ref "CH5-") (pin "1") (pinfunction "P_1") (pintype "passive"))
      (node (ref "U5") (pin "5") (pinfunction "-VOUT_5") (pintype "power_in"))
    )
    (net (code "30") (name "CH6+") (class "Default")
      (node (ref "CH6+") (pin "1") (pinfunction "P_1") (pintype "passive"))
      (node (ref "U6") (pin "6") (pinfunction "+VOUT_6") (pintype "power_in"))
    )
    (net (code "31") (name "CH6-") (class "Default")
      (node (ref "C17") (pin "1") (pinfunction "1_1") (pintype "passive"))
      (node (ref "CH6-") (pin "1") (pinfunction "P_1") (pintype "passive"))
      (node (ref "U6") (pin "5") (pinfunction "-VOUT_5") (pintype "power_in"))
    )
    (net (code "32") (name "DIM1") (class "Default")
      (node (ref "R6") (pin "2") (pinfunction "2_2") (pintype "passive"))
      (node (ref "U1") (pin "2") (pinfunction "ANALOGUE_DIM_2") (pintype "bidirectional"))
      (node (ref "U7") (pin "7") (pinfunction "VOUT_G_7") (pintype "bidirectional"))
    )
    (net (code "33") (name "DIM2") (class "Default")
      (node (ref "R7") (pin "2") (pinfunction "2_2") (pintype "passive"))
      (node (ref "U2") (pin "2") (pinfunction "ANALOGUE_DIM_2") (pintype "bidirectional"))
      (node (ref "U7") (pin "6") (pinfunction "VOUT_E_6") (pintype "bidirectional"))
    )
    (net (code "34") (name "DIM3") (class "Default")
      (node (ref "R8") (pin "2") (pinfunction "2_2") (pintype "passive"))
      (node (ref "U3") (pin "2") (pinfunction "ANALOGUE_DIM_2") (pintype "bidirectional"))
      (node (ref "U7") (pin "5") (pinfunction "VOUT_C_5") (pintype "bidirectional"))
    )
    (net (code "35") (name "DIM4") (class "Default")
      (node (ref "R9") (pin "2") (pinfunction "2_2") (pintype "passive"))
      (node (ref "U4") (pin "2") (pinfunction "ANALOGUE_DIM_2") (pintype "bidirectional"))
      (node (ref "U7") (pin "4") (pinfunction "VOUT_A_4") (pintype "bidirectional"))
    )
    (net (code "36") (name "DIM5") (class "Default")
      (node (ref "R14") (pin "2") (pinfunction "2_2") (pintype "passive"))
      (node (ref "U5") (pin "2") (pinfunction "ANALOGUE_DIM_2") (pintype "bidirectional"))
      (node (ref "U7") (pin "10") (pinfunction "VOUT_H_10") (pintype "bidirectional"))
    )
    (net (code "37") (name "DIM6") (class "Default")
      (node (ref "R26") (pin "2") (pinfunction "2_2") (pintype "passive"))
      (node (ref "U6") (pin "2") (pinfunction "ANALOGUE_DIM_2") (pintype "bidirectional"))
      (node (ref "U7") (pin "11") (pinfunction "VOUT_F_11") (pintype "bidirectional"))
    )
    (net (code "38") (name "GND") (class "Default")
      (node (ref "C1") (pin "2") (pinfunction "2_2") (pintype "passive"))
      (node (ref "C10") (pin "2") (pinfunction "2_2") (pintype "passive"))
      (node (ref "C11") (pin "2") (pinfunction "2_2") (pintype "passive"))
      (node (ref "C12") (pin "-") (pinfunction "2(-)_-") (pintype "passive"))
      (node (ref "C13") (pin "2") (pinfunction "2_2") (pintype "passive"))
      (node (ref "C14") (pin "2") (pinfunction "2_2") (pintype "passive"))
      (node (ref "C15") (pin "-") (pinfunction "2(-)_-") (pintype "passive"))
      (node (ref "C16") (pin "2") (pinfunction "2_2") (pintype "passive"))
      (node (ref "C17") (pin "2") (pinfunction "2_2") (pintype "passive"))
      (node (ref "C18") (pin "-") (pinfunction "2(-)_-") (pintype "passive"))
      (node (ref "C19") (pin "2") (pinfunction "2_2") (pintype "passive"))
      (node (ref "C2") (pin "2") (pinfunction "2_2") (pintype "passive"))
      (node (ref "C20") (pin "2") (pinfunction "2_2") (pintype "passive"))
      (node (ref "C21") (pin "2") (pinfunction "2_2") (pintype "passive"))
      (node (ref "C25") (pin "2") (pinfunction "2_2") (pintype "passive"))
      (node (ref "C27") (pin "2") (pinfunction "2_2") (pintype "passive"))
      (node (ref "C28") (pin "2") (pinfunction "2_2") (pintype "passive"))
      (node (ref "C29") (pin "2") (pinfunction "2_2") (pintype "passive"))
      (node (ref "C3") (pin "-") (pinfunction "2(-)_-") (pintype "passive"))
      (node (ref "C30") (pin "2") (pinfunction "2_2") (pintype "passive"))
      (node (ref "C31") (pin "2") (pinfunction "2_2") (pintype "passive"))
      (node (ref "C32") (pin "2") (pinfunction "2_2") (pintype "passive"))
      (node (ref "C33") (pin "2") (pinfunction "2_2") (pintype "passive"))
      (node (ref "C34") (pin "2") (pinfunction "2_2") (pintype "passive"))
      (node (ref "C36") (pin "2") (pinfunction "2_2") (pintype "passive"))
      (node (ref "C37") (pin "2") (pinfunction "2_2") (pintype "passive"))
      (node (ref "C38") (pin "2") (pinfunction "2_2") (pintype "passive"))
      (node (ref "C4") (pin "2") (pinfunction "2_2") (pintype "passive"))
      (node (ref "C5") (pin "2") (pinfunction "2_2") (pintype "passive"))
      (node (ref "C6") (pin "-") (pinfunction "2(-)_-") (pintype "passive"))
      (node (ref "C7") (pin "2") (pinfunction "2_2") (pintype "passive"))
      (node (ref "C8") (pin "2") (pinfunction "2_2") (pintype "passive"))
      (node (ref "C9") (pin "-") (pinfunction "2(-)_-") (pintype "passive"))
      (node (ref "CR2") (pin "2") (pinfunction "P$1_2") (pintype "bidirectional"))
      (node (ref "D1") (pin "C") (pinfunction "C_C") (pintype "passive"))
      (node (ref "J1") (pin "4") (pinfunction "GND_4") (pintype "bidirectional"))
      (node (ref "J4") (pin "BLK") (pinfunction "GND_BLK") (pintype "power_in"))
      (node (ref "R29") (pin "1") (pinfunction "1_1") (pintype "passive"))
      (node (ref "R56") (pin "1") (pinfunction "1_1") (pintype "passive"))
      (node (ref "R57") (pin "1") (pinfunction "1_1") (pintype "passive"))
      (node (ref "R58") (pin "1") (pinfunction "1_1") (pintype "passive"))
      (node (ref "R59") (pin "1") (pinfunction "1_1") (pintype "passive"))
      (node (ref "R60") (pin "1") (pinfunction "1_1") (pintype "passive"))
      (node (ref "R61") (pin "1") (pinfunction "1_1") (pintype "passive"))
      (node (ref "R62") (pin "2") (pinfunction "2_2") (pintype "passive"))
      (node (ref "U1") (pin "4") (pinfunction "GND_4") (pintype "power_in"))
      (node (ref "U10") (pin "2") (pinfunction "GND1_2") (pintype "bidirectional"))
      (node (ref "U10") (pin "7") (pinfunction "GND1_7") (pintype "bidirectional"))
      (node (ref "U10") (pin "8") (pinfunction "GND1_8") (pintype "bidirectional"))
      (node (ref "U11") (pin "2") (pinfunction "GND_2") (pintype "power_in"))
      (node (ref "U11") (pin "21") (pinfunction "GND_21") (pintype "power_in"))
      (node (ref "U12") (pin "1") (pinfunction "GND_1") (pintype "power_in"))
      (node (ref "U14") (pin "14") (pinfunction "GND_14") (pintype "power_in"))
      (node (ref "U14") (pin "25") (pinfunction "EXTCLK_25") (pintype "input"))
      (node (ref "U2") (pin "4") (pinfunction "GND_4") (pintype "power_in"))
      (node (ref "U3") (pin "4") (pinfunction "GND_4") (pintype "power_in"))
      (node (ref "U4") (pin "4") (pinfunction "GND_4") (pintype "power_in"))
      (node (ref "U5") (pin "4") (pinfunction "GND_4") (pintype "power_in"))
      (node (ref "U6") (pin "4") (pinfunction "GND_4") (pintype "power_in"))
      (node (ref "U7") (pin "1") (pinfunction "~{LDAC}_1") (pintype "bidirectional"))
      (node (ref "U7") (pin "14") (pinfunction "GND_14") (pintype "bidirectional"))
      (node (ref "U8") (pin "5") (pinfunction "GND2_5") (pintype "power_in"))
      (node (ref "U9") (pin "28") (pinfunction "VSS_28") (pintype "power_in"))
    )
    (net (code "39") (name "I2C_3V3") (class "Default")
      (node (ref "C24") (pin "1") (pinfunction "1_1") (pintype "passive"))
      (node (ref "J2") (pin "5") (pinfunction "5_5") (pintype "bidirectional"))
      (node (ref "J3") (pin "5") (pinfunction "5_5") (pintype "bidirectional"))
      (node (ref "J7") (pin "3V3") (pinfunction "3V3_3V3") (pintype "bidirectional"))
      (node (ref "R12") (pin "2") (pinfunction "2_2") (pintype "passive"))
      (node (ref "R13") (pin "2") (pinfunction "2_2") (pintype "passive"))
      (node (ref "U8") (pin "1") (pinfunction "VCC1_1") (pintype "power_in"))
    )
    (net (code "40") (name "I2C_GND") (class "Default")
      (node (ref "C24") (pin "2") (pinfunction "2_2") (pintype "passive"))
      (node (ref "J2") (pin "1") (pinfunction "1_1") (pintype "bidirectional"))
      (node (ref "J3") (pin "1") (pinfunction "1_1") (pintype "bidirectional"))
      (node (ref "J7") (pin "GND") (pinfunction "GND_GND") (pintype "bidirectional"))
      (node (ref "U8") (pin "4") (pinfunction "GND1_4") (pintype "power_in"))
    )
    (net (code "41") (name "I2C_IO") (class "Default")
      (node (ref "J2") (pin "2") (pinfunction "2_2") (pintype "bidirectional"))
      (node (ref "J3") (pin "2") (pinfunction "2_2") (pintype "bidirectional"))
    )
    (net (code "42") (name "Net-(D1-PadA)") (class "Default")
      (node (ref "D1") (pin "A") (pinfunction "A_A") (pintype "passive"))
      (node (ref "R27") (pin "1") (pinfunction "1_1") (pintype "passive"))
    )
    (net (code "43") (name "Net-(U1-+VIN)") (class "Default")
      (node (ref "C1") (pin "1") (pinfunction "1_1") (pintype "passive"))
      (node (ref "L1") (pin "2") (pinfunction "2_2") (pintype "passive"))
      (node (ref "U1") (pin "1") (pinfunction "+VIN_1") (pintype "power_in"))
    )
    (net (code "44") (name "Net-(U2-+VIN)") (class "Default")
      (node (ref "C4") (pin "1") (pinfunction "1_1") (pintype "passive"))
      (node (ref "L2") (pin "2") (pinfunction "2_2") (pintype "passive"))
      (node (ref "U2") (pin "1") (pinfunction "+VIN_1") (pintype "power_in"))
    )
    (net (code "45") (name "Net-(U3-+VIN)") (class "Default")
      (node (ref "C7") (pin "1") (pinfunction "1_1") (pintype "passive"))
      (node (ref "L3") (pin "2") (pinfunction "2_2") (pintype "passive"))
      (node (ref "U3") (pin "1") (pinfunction "+VIN_1") (pintype "power_in"))
    )
    (net (code "46") (name "Net-(U4-+VIN)") (class "Default")
      (node (ref "C10") (pin "1") (pinfunction "1_1") (pintype "passive"))
      (node (ref "L4") (pin "2") (pinfunction "2_2") (pintype "passive"))
      (node (ref "U4") (pin "1") (pinfunction "+VIN_1") (pintype "power_in"))
    )
    (net (code "47") (name "Net-(U5-+VIN)") (class "Default")
      (node (ref "C13") (pin "1") (pinfunction "1_1") (pintype "passive"))
      (node (ref "L5") (pin "2") (pinfunction "2_2") (pintype "passive"))
      (node (ref "U5") (pin "1") (pinfunction "+VIN_1") (pintype "power_in"))
    )
    (net (code "48") (name "Net-(U6-+VIN)") (class "Default")
      (node (ref "C16") (pin "1") (pinfunction "1_1") (pintype "passive"))
      (node (ref "L6") (pin "2") (pinfunction "2_2") (pintype "passive"))
      (node (ref "U6") (pin "1") (pinfunction "+VIN_1") (pintype "power_in"))
    )
    (net (code "49") (name "Net-(U9-VCCD)") (class "Default")
      (node (ref "C33") (pin "1") (pinfunction "1_1") (pintype "passive"))
      (node (ref "U9") (pin "26") (pinfunction "VCCD_26") (pintype "power_in"))
    )
    (net (code "50") (name "Net-(U11-3V3)") (class "Default")
      (node (ref "C30") (pin "1") (pinfunction "1_1") (pintype "passive"))
      (node (ref "C34") (pin "1") (pinfunction "1_1") (pintype "passive"))
      (node (ref "R17") (pin "1") (pinfunction "1_1") (pintype "passive"))
      (node (ref "U11") (pin "24") (pinfunction "3V3_24") (pintype "power_in"))
    )
    (net (code "51") (name "P0[7]") (class "Default")
      (node (ref "R25") (pin "1") (pinfunction "1_1") (pintype "passive"))
      (node (ref "U9") (pin "24") (pinfunction "P0[7]_24") (pintype "bidirectional"))
    )
    (net (code "52") (name "P2[6]") (class "Default")
      (node (ref "R20") (pin "1") (pinfunction "1_1") (pintype "passive"))
      (node (ref "U9") (pin "9") (pinfunction "P2[6]_9") (pintype "bidirectional"))
    )
    (net (code "53") (name "P2[7]") (class "Default")
      (node (ref "R21") (pin "1") (pinfunction "1_1") (pintype "passive"))
      (node (ref "U9") (pin "10") (pinfunction "P2[7]_10") (pintype "bidirectional"))
    )
    (net (code "54") (name "PHOTON_A0") (class "Default")
      (node (ref "R24") (pin "1") (pinfunction "1_1") (pintype "passive"))
      (node (ref "U11") (pin "12") (pinfunction "A0_12") (pintype "bidirectional"))
    )
    (net (code "55") (name "PHOTON_D2") (class "Default")
      (node (ref "R22") (pin "1") (pinfunction "1_1") (pintype "passive"))
      (node (ref "U11") (pin "15") (pinfunction "D2_15") (pintype "bidirectional"))
    )
    (net (code "56") (name "PHOTON_D3") (class "Default")
      (node (ref "R23") (pin "1") (pinfunction "1_1") (pintype "passive"))
      (node (ref "U11") (pin "16") (pinfunction "D3_16") (pintype "bidirectional"))
    )
    (net (code "57") (name "PHOTON_D4") (class "Default")
      (node (ref "U11") (pin "17") (pinfunction "D4_17") (pintype "bidirectional"))
    )
    (net (code "58") (name "PHOTON_RX") (class "Default")
      (node (ref "R18") (pin "1") (pinfunction "1_1") (pintype "passive"))
      (node (ref "U11") (pin "4") (pinfunction "RX_4") (pintype "bidirectional"))
    )
    (net (code "59") (name "PHOTON_SCL") (class "Default")
      (node (ref "R5") (pin "1") (pinfunction "1_1") (pintype "passive"))
      (node (ref "U11") (pin "14") (pinfunction "D1_14") (pintype "bidirectional"))
    )
    (net (code "60") (name "PHOTON_SDA") (class "Default")
      (node (ref "R4") (pin "1") (pinfunction "1_1") (pintype "passive"))
      (node (ref "U11") (pin "13") (pinfunction "D0_13") (pintype "bidirectional"))
    )
    (net (code "61") (name "PHOTON_TX") (class "Default")
      (node (ref "R19") (pin "1") (pinfunction "1_1") (pintype "passive"))
      (node (ref "U11") (pin "3") (pinfunction "TX_3") (pintype "bidirectional"))
    )
    (net (code "62") (name "PWM1") (class "Default")
      (node (ref "U1") (pin "3") (pinfunction "PWM/ON/OFF_3") (pintype "bidirectional"))
      (node (ref "U14") (pin "12") (pinfunction "PWM6_12") (pintype "output"))
    )
    (net (code "63") (name "PWM2") (class "Default")
      (node (ref "U14") (pin "11") (pinfunction "PWM5_11") (pintype "output"))
      (node (ref "U2") (pin "3") (pinfunction "PWM/ON/OFF_3") (pintype "bidirectional"))
    )
    (net (code "64") (name "PWM3") (class "Default")
      (node (ref "U14") (pin "10") (pinfunction "PWM4_10") (pintype "output"))
      (node (ref "U3") (pin "3") (pinfunction "PWM/ON/OFF_3") (pintype "bidirectional"))
    )
    (net (code "65") (name "PWM4") (class "Default")
      (node (ref "U14") (pin "9") (pinfunction "PWM3_9") (pintype "output"))
      (node (ref "U4") (pin "3") (pinfunction "PWM/ON/OFF_3") (pintype "bidirectional"))
    )
    (net (code "66") (name "PWM5") (class "Default")
      (node (ref "U14") (pin "8") (pinfunction "PWM2_8") (pintype "output"))
      (node (ref "U5") (pin "3") (pinfunction "PWM/ON/OFF_3") (pintype "bidirectional"))
    )
    (net (code "67") (name "PWM6") (class "Default")
      (node (ref "U14") (pin "7") (pinfunction "PWM1_7") (pintype "output"))
      (node (ref "U6") (pin "3") (pinfunction "PWM/ON/OFF_3") (pintype "bidirectional"))
    )
    (net (code "68") (name "REG_3V3") (class "Default")
      (node (ref "C20") (pin "1") (pinfunction "1_1") (pintype "passive"))
      (node (ref "J8") (pin "1") (pinfunction "1_1") (pintype "bidirectional"))
      (node (ref "U12") (pin "3") (pinfunction "OUT_3") (pintype "output"))
    )
    (net (code "69") (name "SCB0_I2C_SCL") (class "Default")
      (node (ref "R2") (pin "1") (pinfunction "1_1") (pintype "passive"))
      (node (ref "U9") (pin "15") (pinfunction "P4[0]_15") (pintype "bidirectional"))
    )
    (net (code "70") (name "SCB0_I2C_SDA") (class "Default")
      (node (ref "R1") (pin "1") (pinfunction "1_1") (pintype "passive"))
      (node (ref "U9") (pin "16") (pinfunction "P4[1]_16") (pintype "bidirectional"))
    )
    (net (code "71") (name "SCB1_RX[0]_SCL[0]") (class "Default")
      (node (ref "R15") (pin "1") (pinfunction "1_1") (pintype "passive"))
      (node (ref "R31") (pin "1") (pinfunction "1_1") (pintype "passive"))
      (node (ref "U9") (pin "11") (pinfunction "P3[0]_11") (pintype "bidirectional"))
    )
    (net (code "72") (name "SCB1_TX[0]_SDA[0]") (class "Default")
      (node (ref "R16") (pin "1") (pinfunction "1_1") (pintype "passive"))
      (node (ref "R30") (pin "1") (pinfunction "1_1") (pintype "passive"))
      (node (ref "U9") (pin "12") (pinfunction "P3[1]_12") (pintype "bidirectional"))
    )
    (net (code "73") (name "SCL") (class "Default")
      (node (ref "R2") (pin "2") (pinfunction "2_2") (pintype "passive"))
      (node (ref "R33") (pin "2") (pinfunction "2_2") (pintype "passive"))
      (node (ref "R5") (pin "2") (pinfunction "2_2") (pintype "passive"))
      (node (ref "U14") (pin "26") (pinfunction "SCL_26") (pintype "bidirectional"))
      (node (ref "U7") (pin "16") (pinfunction "SCL_16") (pintype "bidirectional"))
    )
    (net (code "74") (name "SCL1") (class "Default")
      (node (ref "J2") (pin "3") (pinfunction "3_3") (pintype "bidirectional"))
      (node (ref "J3") (pin "3") (pinfunction "3_3") (pintype "bidirectional"))
      (node (ref "J7") (pin "SCL") (pinfunction "SCL_SCL") (pintype "bidirectional"))
      (node (ref "R12") (pin "1") (pinfunction "1_1") (pintype "passive"))
      (node (ref "U8") (pin "3") (pinfunction "SCL1_3") (pintype "bidirectional"))
    )
    (net (code "75") (name "SCL2") (class "Default")
      (node (ref "R10") (pin "1") (pinfunction "1_1") (pintype "passive"))
      (node (ref "R31") (pin "2") (pinfunction "2_2") (pintype "passive"))
      (node (ref "R33") (pin "1") (pinfunction "1_1") (pintype "passive"))
      (node (ref "U8") (pin "6") (pinfunction "SCL2_6") (pintype "bidirectional"))
    )
    (net (code "76") (name "SDA") (class "Default")
      (node (ref "R1") (pin "2") (pinfunction "2_2") (pintype "passive"))
      (node (ref "R32") (pin "2") (pinfunction "2_2") (pintype "passive"))
      (node (ref "R4") (pin "2") (pinfunction "2_2") (pintype "passive"))
      (node (ref "U14") (pin "27") (pinfunction "SDA_27") (pintype "bidirectional"))
      (node (ref "U7") (pin "15") (pinfunction "SDA_15") (pintype "bidirectional"))
    )
    (net (code "77") (name "SDA1") (class "Default")
      (node (ref "J2") (pin "4") (pinfunction "4_4") (pintype "bidirectional"))
      (node (ref "J3") (pin "4") (pinfunction "4_4") (pintype "bidirectional"))
      (node (ref "J7") (pin "SDA") (pinfunction "SDA_SDA") (pintype "bidirectional"))
      (node (ref "R13") (pin "1") (pinfunction "1_1") (pintype "passive"))
      (node (ref "U8") (pin "2") (pinfunction "SDA1_2") (pintype "bidirectional"))
    )
    (net (code "78") (name "SDA2") (class "Default")
      (node (ref "R11") (pin "1") (pinfunction "1_1") (pintype "passive"))
      (node (ref "R30") (pin "2") (pinfunction "2_2") (pintype "passive"))
      (node (ref "R32") (pin "1") (pinfunction "1_1") (pintype "passive"))
      (node (ref "U8") (pin "7") (pinfunction "SDA2_7") (pintype "bidirectional"))
    )
    (net (code "79") (name "SWD_CLK[0]") (class "Default")
      (node (ref "J1") (pin "2") (pinfunction "SCLK_2") (pintype "bidirectional"))
      (node (ref "U9") (pin "14") (pinfunction "P3[3]_14") (pintype "bidirectional"))
    )
    (net (code "80") (name "SWD_IO[0]") (class "Default")
      (node (ref "J1") (pin "1") (pinfunction "SDAT_1") (pintype "bidirectional"))
      (node (ref "U9") (pin "13") (pinfunction "P3[2]_13") (pintype "bidirectional"))
    )
    (net (code "81") (name "UART_DE") (class "Default")
      (node (ref "R20") (pin "2") (pinfunction "2_2") (pintype "passive"))
      (node (ref "R22") (pin "2") (pinfunction "2_2") (pintype "passive"))
      (node (ref "U10") (pin "5") (pinfunction "DE_5") (pintype "bidirectional"))
    )
    (net (code "82") (name "UART_RX") (class "Default")
      (node (ref "R15") (pin "2") (pinfunction "2_2") (pintype "passive"))
      (node (ref "R18") (pin "2") (pinfunction "2_2") (pintype "passive"))
      (node (ref "U10") (pin "3") (pinfunction "RXD_3") (pintype "bidirectional"))
    )
    (net (code "83") (name "UART_TX") (class "Default")
      (node (ref "R16") (pin "2") (pinfunction "2_2") (pintype "passive"))
      (node (ref "R19") (pin "2") (pinfunction "2_2") (pintype "passive"))
      (node (ref "U10") (pin "6") (pinfunction "TXD_6") (pintype "bidirectional"))
    )
    (net (code "84") (name "VDDD") (class "Default")
      (node (ref "C31") (pin "1") (pinfunction "1_1") (pintype "passive"))
      (node (ref "C32") (pin "1") (pinfunction "1_1") (pintype "passive"))
      (node (ref "J1") (pin "5") (pinfunction "VTARG_5") (pintype "bidirectional"))
      (node (ref "R3") (pin "2") (pinfunction "2_2") (pintype "passive"))
      (node (ref "U9") (pin "27") (pinfunction "VDDD_27") (pintype "power_in"))
    )
    (net (code "85") (name "XRES") (class "Default")
      (node (ref "J1") (pin "3") (pinfunction "XRES_3") (pintype "bidirectional"))
      (node (ref "U9") (pin "25") (pinfunction "XRES_25") (pintype "input"))
    )
    (net (code "86") (name "unconnected-(J2-Pad6)") (class "Default")
      (node (ref "J2") (pin "6") (pinfunction "6_6") (pintype "bidirectional"))
    )
    (net (code "87") (name "unconnected-(J3-Pad6)") (class "Default")
      (node (ref "J3") (pin "6") (pinfunction "6_6") (pintype "bidirectional"))
    )
    (net (code "88") (name "unconnected-(J5-Pad5)") (class "Default")
      (node (ref "J5") (pin "5") (pinfunction "5_5") (pintype "bidirectional"))
    )
    (net (code "89") (name "unconnected-(J6-Pad5)") (class "Default")
      (node (ref "J6") (pin "5") (pinfunction "5_5") (pintype "bidirectional"))
    )
    (net (code "90") (name "unconnected-(SW1-P1-Pad4)") (class "Default")
      (node (ref "SW1") (pin "4") (pinfunction "P1_4") (pintype "passive"))
    )
    (net (code "91") (name "unconnected-(SW1-S1-Pad2)") (class "Default")
      (node (ref "SW1") (pin "2") (pinfunction "S1_2") (pintype "passive"))
    )
    (net (code "92") (name "unconnected-(U7-ADDR0-Pad2)") (class "Default")
      (node (ref "U7") (pin "2") (pinfunction "ADDR0_2") (pintype "bidirectional"))
    )
    (net (code "93") (name "unconnected-(U7-VOUT_B-Pad13)") (class "Default")
      (node (ref "U7") (pin "13") (pinfunction "VOUT_B_13") (pintype "bidirectional"))
    )
    (net (code "94") (name "unconnected-(U7-VOUT_D-Pad12)") (class "Default")
      (node (ref "U7") (pin "12") (pinfunction "VOUT_D_12") (pintype "bidirectional"))
    )
    (net (code "95") (name "unconnected-(U9-P0[0]-Pad19)") (class "Default")
      (node (ref "U9") (pin "19") (pinfunction "P0[0]_19") (pintype "bidirectional"))
    )
    (net (code "96") (name "unconnected-(U9-P0[1]-Pad20)") (class "Default")
      (node (ref "U9") (pin "20") (pinfunction "P0[1]_20") (pintype "bidirectional"))
    )
    (net (code "97") (name "unconnected-(U9-P0[2]-Pad21)") (class "Default")
      (node (ref "U9") (pin "21") (pinfunction "P0[2]_21") (pintype "bidirectional"))
    )
    (net (code "98") (name "unconnected-(U9-P0[3]-Pad22)") (class "Default")
      (node (ref "U9") (pin "22") (pinfunction "P0[3]_22") (pintype "bidirectional"))
    )
    (net (code "99") (name "unconnected-(U9-P0[6]-Pad23)") (class "Default")
      (node (ref "U9") (pin "23") (pinfunction "P0[6]_23") (pintype "bidirectional"))
    )
    (net (code "100") (name "unconnected-(U9-P1[0]-Pad1)") (class "Default")
      (node (ref "U9") (pin "1") (pinfunction "P1[0]_1") (pintype "bidirectional"))
    )
    (net (code "101") (name "unconnected-(U9-P1[1]-Pad2)") (class "Default")
      (node (ref "U9") (pin "2") (pinfunction "P1[1]_2") (pintype "bidirectional"))
    )
    (net (code "102") (name "unconnected-(U9-P1[2]-Pad3)") (class "Default")
      (node (ref "U9") (pin "3") (pinfunction "P1[2]_3") (pintype "bidirectional"))
    )
    (net (code "103") (name "unconnected-(U9-P1[7]-Pad4)") (class "Default")
      (node (ref "U9") (pin "4") (pinfunction "P1[7]_4") (pintype "bidirectional"))
    )
    (net (code "104") (name "unconnected-(U9-P2[2]-Pad5)") (class "Default")
      (node (ref "U9") (pin "5") (pinfunction "P2[2]_5") (pintype "bidirectional"))
    )
    (net (code "105") (name "unconnected-(U9-P2[3]-Pad6)") (class "Default")
      (node (ref "U9") (pin "6") (pinfunction "P2[3]_6") (pintype "bidirectional"))
    )
    (net (code "106") (name "unconnected-(U9-P2[4]-Pad7)") (class "Default")
      (node (ref "U9") (pin "7") (pinfunction "P2[4]_7") (pintype "bidirectional"))
    )
    (net (code "107") (name "unconnected-(U9-P2[5]-Pad8)") (class "Default")
      (node (ref "U9") (pin "8") (pinfunction "P2[5]_8") (pintype "bidirectional"))
    )
    (net (code "108") (name "unconnected-(U9-P4[2]-Pad17)") (class "Default")
      (node (ref "U9") (pin "17") (pinfunction "P4[2]_17") (pintype "bidirectional"))
    )
    (net (code "109") (name "unconnected-(U9-P4[3]-Pad18)") (class "Default")
      (node (ref "U9") (pin "18") (pinfunction "P4[3]_18") (pintype "bidirectional"))
    )
    (net (code "110") (name "unconnected-(U11-A1-Pad11)") (class "Default")
      (node (ref "U11") (pin "11") (pinfunction "A1_11") (pintype "bidirectional"))
    )
    (net (code "111") (name "unconnected-(U11-A2-Pad10)") (class "Default")
      (node (ref "U11") (pin "10") (pinfunction "A2_10") (pintype "bidirectional"))
    )
    (net (code "112") (name "unconnected-(U11-A3-Pad9)") (class "Default")
      (node (ref "U11") (pin "9") (pinfunction "A3_9") (pintype "bidirectional"))
    )
    (net (code "113") (name "unconnected-(U11-A4-Pad8)") (class "Default")
      (node (ref "U11") (pin "8") (pinfunction "A4_8") (pintype "bidirectional"))
    )
    (net (code "114") (name "unconnected-(U11-A5-Pad7)") (class "Default")
      (node (ref "U11") (pin "7") (pinfunction "A5_7") (pintype "bidirectional"))
    )
    (net (code "115") (name "unconnected-(U11-D5-Pad18)") (class "Default")
      (node (ref "U11") (pin "18") (pinfunction "D5_18") (pintype "bidirectional"))
    )
    (net (code "116") (name "unconnected-(U11-D6-Pad19)") (class "Default")
      (node (ref "U11") (pin "19") (pinfunction "D6_19") (pintype "bidirectional"))
    )
    (net (code "117") (name "unconnected-(U11-D7-Pad20)") (class "Default")
      (node (ref "U11") (pin "20") (pinfunction "D7_20") (pintype "bidirectional"))
    )
    (net (code "118") (name "unconnected-(U11-DAC-Pad6)") (class "Default")
      (node (ref "U11") (pin "6") (pinfunction "DAC_6") (pintype "bidirectional"))
    )
    (net (code "119") (name "unconnected-(U11-WKP-Pad5)") (class "Default")
      (node (ref "U11") (pin "5") (pinfunction "WKP_5") (pintype "bidirectional"))
    )
    (net (code "120") (name "unconnected-(U11-~{RST}-Pad23)") (class "Default")
      (node (ref "U11") (pin "23") (pinfunction "~{RST}_23") (pintype "bidirectional"))
    )
    (net (code "121") (name "unconnected-(U12-NC-Pad5)") (class "Default")
      (node (ref "U12") (pin "5") (pinfunction "NC_5") (pintype "passive"))
    )
    (net (code "122") (name "unconnected-(U12-NC_2-Pad4)") (class "Default")
      (node (ref "U12") (pin "4") (pinfunction "NC_2_4") (pintype "passive"))
    )
    (net (code "123") (name "unconnected-(U14-PWM0-Pad6)") (class "Default")
      (node (ref "U14") (pin "6") (pinfunction "PWM0_6") (pintype "output"))
    )
    (net (code "124") (name "unconnected-(U14-PWM7-Pad13)") (class "Default")
      (node (ref "U14") (pin "13") (pinfunction "PWM7_13") (pintype "output"))
    )
    (net (code "125") (name "unconnected-(U14-PWM8-Pad15)") (class "Default")
      (node (ref "U14") (pin "15") (pinfunction "PWM8_15") (pintype "output"))
    )
    (net (code "126") (name "unconnected-(U14-PWM9-Pad16)") (class "Default")
      (node (ref "U14") (pin "16") (pinfunction "PWM9_16") (pintype "output"))
    )
    (net (code "127") (name "unconnected-(U14-PWM10-Pad17)") (class "Default")
      (node (ref "U14") (pin "17") (pinfunction "PWM10_17") (pintype "output"))
    )
    (net (code "128") (name "unconnected-(U14-PWM11-Pad18)") (class "Default")
      (node (ref "U14") (pin "18") (pinfunction "PWM11_18") (pintype "output"))
    )
    (net (code "129") (name "unconnected-(U14-PWM12-Pad19)") (class "Default")
      (node (ref "U14") (pin "19") (pinfunction "PWM12_19") (pintype "output"))
    )
    (net (code "130") (name "unconnected-(U14-PWM13-Pad20)") (class "Default")
      (node (ref "U14") (pin "20") (pinfunction "PWM13_20") (pintype "output"))
    )
    (net (code "131") (name "unconnected-(U14-PWM14-Pad21)") (class "Default")
      (node (ref "U14") (pin "21") (pinfunction "PWM14_21") (pintype "output"))
    )
    (net (code "132") (name "unconnected-(U14-PWM15-Pad22)") (class "Default")
      (node (ref "U14") (pin "22") (pinfunction "PWM15_22") (pintype "output"))
    )
  )
)
